# MCU.net
KiCad netlist of a schematic drawn in Altium Designer
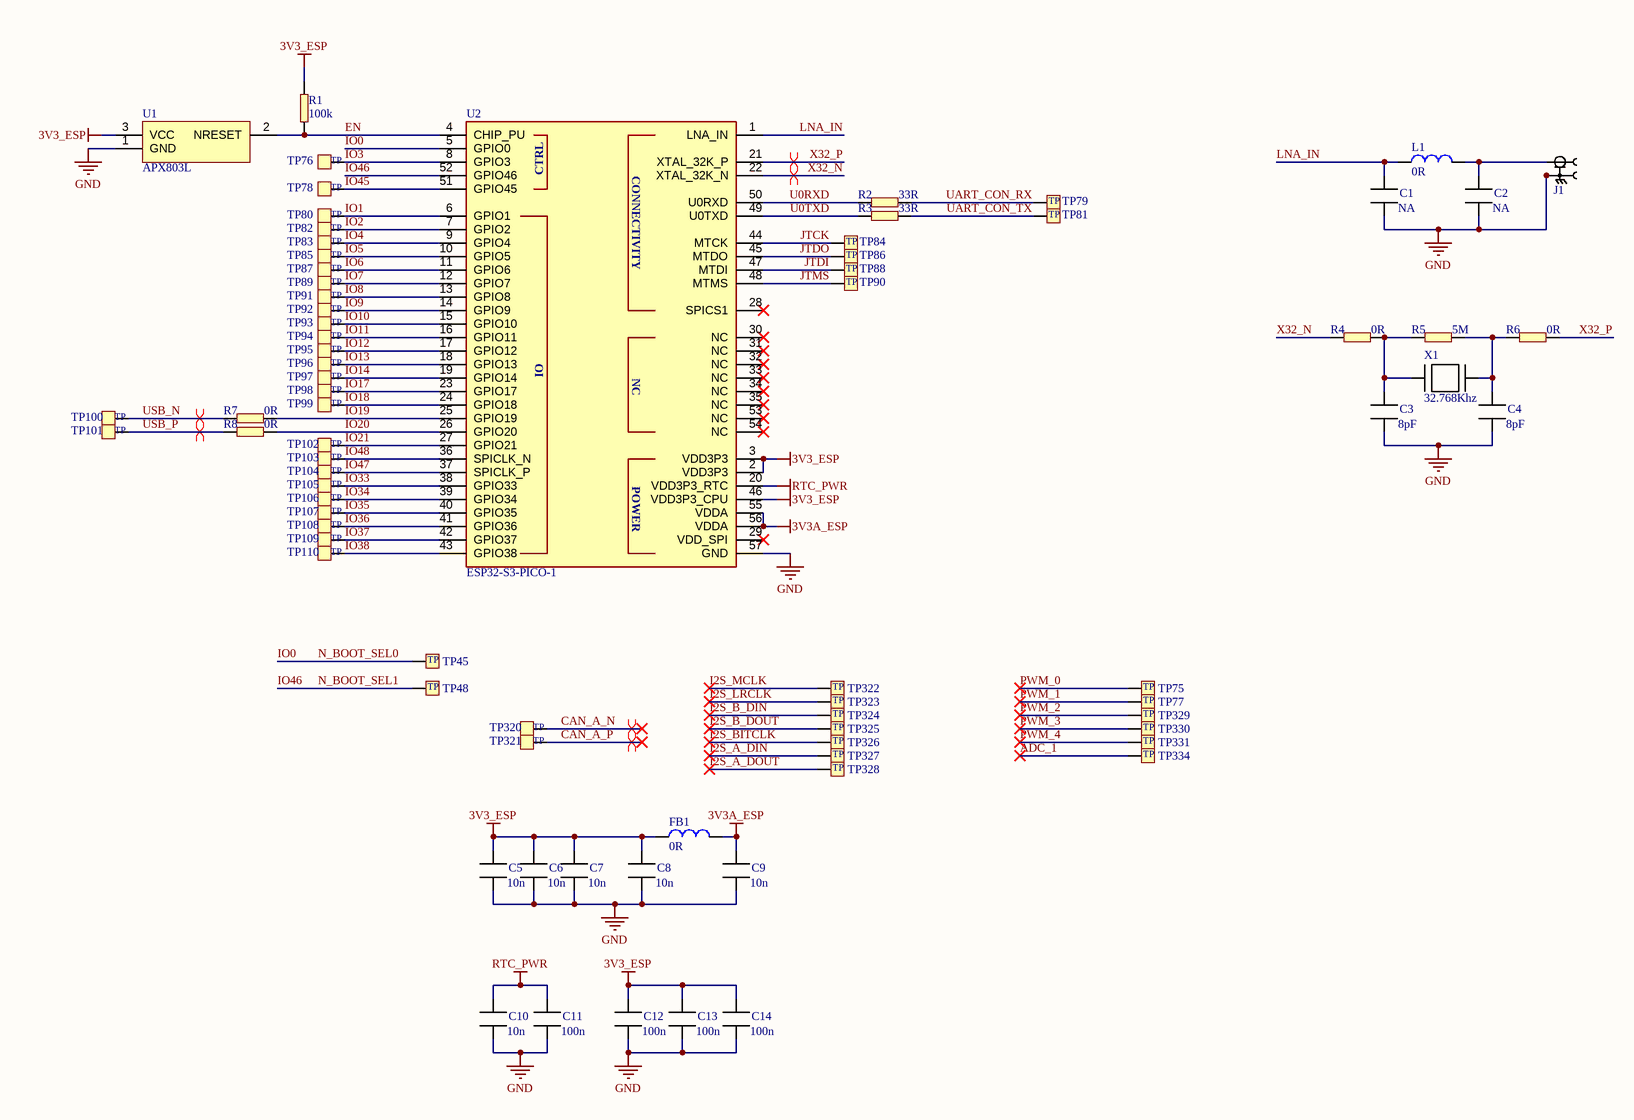
[diagram p0: MCU.SchDoc]

(export (version "E")
  (design (tool "Eeschema 10.0.6"))
  (components
    (comp (ref "C1")
      (value "NA")
      (footprint "CAPC0603X03L")
      (description "Chip Capacitor, 2-Leads, Body 0.60x0.30mm, IPC High Density")
      (fields (field (name "Comment") "ERP_102-1"))
      (libsource (lib "Capacitor") (part "MLCC_0201"))
    )
    (comp (ref "C2")
      (value "NA")
      (footprint "CAPC0603X03L")
      (description "Chip Capacitor, 2-Leads, Body 0.60x0.30mm, IPC High Density")
      (fields (field (name "Comment") "ERP_102-1"))
      (libsource (lib "Capacitor") (part "MLCC_0201"))
    )
    (comp (ref "C3")
      (value "8pF")
      (footprint "CAPC0603X03L")
      (description "Chip Capacitor, 2-Leads, Body 0.60x0.30mm, IPC High Density")
      (fields (field (name "Comment") "ERP_102-1"))
      (libsource (lib "Capacitor") (part "MLCC_0201"))
    )
    (comp (ref "C4")
      (value "8pF")
      (footprint "CAPC0603X03L")
      (description "Chip Capacitor, 2-Leads, Body 0.60x0.30mm, IPC High Density")
      (fields (field (name "Comment") "ERP_102-1"))
      (libsource (lib "Capacitor") (part "MLCC_0201"))
    )
    (comp (ref "C5")
      (value "10n")
      (footprint "CAPC0603X03L")
      (description "Chip Capacitor, 2-Leads, Body 0.60x0.30mm, IPC High Density")
      (fields (field (name "Comment") "ERP_102-1"))
      (libsource (lib "Capacitor") (part "MLCC_0201"))
    )
    (comp (ref "C6")
      (value "10n")
      (footprint "CAPC0603X03L")
      (description "Chip Capacitor, 2-Leads, Body 0.60x0.30mm, IPC High Density")
      (fields (field (name "Comment") "ERP_102-1"))
      (libsource (lib "Capacitor") (part "MLCC_0201"))
    )
    (comp (ref "C7")
      (value "10n")
      (footprint "CAPC0603X03L")
      (description "Chip Capacitor, 2-Leads, Body 0.60x0.30mm, IPC High Density")
      (fields (field (name "Comment") "ERP_102-1"))
      (libsource (lib "Capacitor") (part "MLCC_0201"))
    )
    (comp (ref "C8")
      (value "10n")
      (footprint "CAPC0603X03L")
      (description "Chip Capacitor, 2-Leads, Body 0.60x0.30mm, IPC High Density")
      (fields (field (name "Comment") "ERP_102-1"))
      (libsource (lib "Capacitor") (part "MLCC_0201"))
    )
    (comp (ref "C9")
      (value "10n")
      (footprint "CAPC0603X03L")
      (description "Chip Capacitor, 2-Leads, Body 0.60x0.30mm, IPC High Density")
      (fields (field (name "Comment") "ERP_102-1"))
      (libsource (lib "Capacitor") (part "MLCC_0201"))
    )
    (comp (ref "C10")
      (value "10n")
      (footprint "CAPC0603X03L")
      (description "Chip Capacitor, 2-Leads, Body 0.60x0.30mm, IPC High Density")
      (fields (field (name "Comment") "ERP_102-1"))
      (libsource (lib "Capacitor") (part "MLCC_0201"))
    )
    (comp (ref "C11")
      (value "100n")
      (footprint "CAPC0603X03L")
      (description "Chip Capacitor, 2-Leads, Body 0.60x0.30mm, IPC High Density")
      (fields (field (name "Comment") "ERP_102-1"))
      (libsource (lib "Capacitor") (part "MLCC_0201"))
    )
    (comp (ref "C12")
      (value "100n")
      (footprint "CAPC0603X03L")
      (description "Chip Capacitor, 2-Leads, Body 0.60x0.30mm, IPC High Density")
      (fields (field (name "Comment") "ERP_102-1"))
      (libsource (lib "Capacitor") (part "MLCC_0201"))
    )
    (comp (ref "C13")
      (value "100n")
      (footprint "CAPC0603X03L")
      (description "Chip Capacitor, 2-Leads, Body 0.60x0.30mm, IPC High Density")
      (fields (field (name "Comment") "ERP_102-1"))
      (libsource (lib "Capacitor") (part "MLCC_0201"))
    )
    (comp (ref "C14")
      (value "100n")
      (footprint "CAPC0603X03L")
      (description "Chip Capacitor, 2-Leads, Body 0.60x0.30mm, IPC High Density")
      (fields (field (name "Comment") "ERP_102-1"))
      (libsource (lib "Capacitor") (part "MLCC_0201"))
    )
    (comp (ref "FB1")
      (value "0R")
      (footprint "INDC0603X03L")
      (description "FERRITE BEAD 0201")
      (fields (field (name "Comment") "ERP_103-3"))
      (libsource (lib "FerriteBead") (part "FB_0201"))
    )
    (comp (ref "J1")
      (value "ERP_148-1")
      (footprint "uFL_50R")
      (description "uFL_50R")
      (libsource (lib "RF_Connector") (part "uFL_50R"))
    )
    (comp (ref "L1")
      (value "0R")
      (footprint "IND_0603")
      (description "IND_0603")
      (fields (field (name "Comment") "ERP_103-3"))
      (libsource (lib "Inductor") (part "IND_0603"))
    )
    (comp (ref "R1")
      (value "100k")
      (footprint "RESC0603X03L")
      (description "RES_0201")
      (fields (field (name "Comment") "ERP_101-1"))
      (libsource (lib "Resistor") (part "RES_0201"))
    )
    (comp (ref "R2")
      (value "33R")
      (footprint "RESC0603X03L")
      (description "RES_0201")
      (fields (field (name "Comment") "ERP_101-1"))
      (libsource (lib "") (part "RES_0201_1"))
    )
    (comp (ref "R3")
      (value "33R")
      (footprint "RESC0603X03L")
      (description "RES_0201")
      (fields (field (name "Comment") "ERP_101-1"))
      (libsource (lib "") (part "RES_0201_1"))
    )
    (comp (ref "R4")
      (value "0R")
      (footprint "RESC0603X03L")
      (description "RES_0201")
      (fields (field (name "Comment") "ERP_101-1"))
      (libsource (lib "") (part "RES_0201_1"))
    )
    (comp (ref "R5")
      (value "5M")
      (footprint "RESC0603X03L")
      (description "RES_0201")
      (fields (field (name "Comment") "ERP_101-1"))
      (libsource (lib "") (part "RES_0201_1"))
    )
    (comp (ref "R6")
      (value "0R")
      (footprint "RESC0603X03L")
      (description "RES_0201")
      (fields (field (name "Comment") "ERP_101-1"))
      (libsource (lib "") (part "RES_0201_1"))
    )
    (comp (ref "R7")
      (value "0R")
      (footprint "RESC0603X03L")
      (description "RES_0201")
      (fields (field (name "Comment") "ERP_101-1"))
      (libsource (lib "") (part "RES_0201_1"))
    )
    (comp (ref "R8")
      (value "0R")
      (footprint "RESC0603X03L")
      (description "RES_0201")
      (fields (field (name "Comment") "ERP_101-1"))
      (libsource (lib "") (part "RES_0201_1"))
    )
    (comp (ref "TP45")
      (value "TP_0P8MM")
      (footprint "TP_0P8MM")
      (description "OSM Footprint 0P8 LGA Ball")
      (libsource (lib "") (part "TP_0P8MM_1"))
    )
    (comp (ref "TP48")
      (value "TP_0P8MM")
      (footprint "TP_0P8MM")
      (description "OSM Footprint 0P8 LGA Ball")
      (libsource (lib "") (part "TP_0P8MM_1"))
    )
    (comp (ref "TP75")
      (value "TP_0P8MM")
      (footprint "TP_0P8MM")
      (description "OSM Footprint 0P8 LGA Ball")
      (libsource (lib "") (part "TP_0P8MM_1"))
    )
    (comp (ref "TP76")
      (value "TP_0P8MM")
      (footprint "TP_0P8MM")
      (description "OSM Footprint 0P8 LGA Ball")
      (libsource (lib "Jumper") (part "TP_0P8MM"))
    )
    (comp (ref "TP77")
      (value "TP_0P8MM")
      (footprint "TP_0P8MM")
      (description "OSM Footprint 0P8 LGA Ball")
      (libsource (lib "") (part "TP_0P8MM_1"))
    )
    (comp (ref "TP78")
      (value "TP_0P8MM")
      (footprint "TP_0P8MM")
      (description "OSM Footprint 0P8 LGA Ball")
      (libsource (lib "Jumper") (part "TP_0P8MM"))
    )
    (comp (ref "TP79")
      (value "TP_0P8MM")
      (footprint "TP_0P8MM")
      (description "OSM Footprint 0P8 LGA Ball")
      (libsource (lib "") (part "TP_0P8MM_1"))
    )
    (comp (ref "TP80")
      (value "TP_0P8MM")
      (footprint "TP_0P8MM")
      (description "OSM Footprint 0P8 LGA Ball")
      (libsource (lib "Jumper") (part "TP_0P8MM"))
    )
    (comp (ref "TP81")
      (value "TP_0P8MM")
      (footprint "TP_0P8MM")
      (description "OSM Footprint 0P8 LGA Ball")
      (libsource (lib "") (part "TP_0P8MM_1"))
    )
    (comp (ref "TP82")
      (value "TP_0P8MM")
      (footprint "TP_0P8MM")
      (description "OSM Footprint 0P8 LGA Ball")
      (libsource (lib "Jumper") (part "TP_0P8MM"))
    )
    (comp (ref "TP83")
      (value "TP_0P8MM")
      (footprint "TP_0P8MM")
      (description "OSM Footprint 0P8 LGA Ball")
      (libsource (lib "Jumper") (part "TP_0P8MM"))
    )
    (comp (ref "TP84")
      (value "TP_0P8MM")
      (footprint "TP_0P8MM")
      (description "OSM Footprint 0P8 LGA Ball")
      (libsource (lib "") (part "TP_0P8MM_1"))
    )
    (comp (ref "TP85")
      (value "TP_0P8MM")
      (footprint "TP_0P8MM")
      (description "OSM Footprint 0P8 LGA Ball")
      (libsource (lib "Jumper") (part "TP_0P8MM"))
    )
    (comp (ref "TP86")
      (value "TP_0P8MM")
      (footprint "TP_0P8MM")
      (description "OSM Footprint 0P8 LGA Ball")
      (libsource (lib "") (part "TP_0P8MM_1"))
    )
    (comp (ref "TP87")
      (value "TP_0P8MM")
      (footprint "TP_0P8MM")
      (description "OSM Footprint 0P8 LGA Ball")
      (libsource (lib "Jumper") (part "TP_0P8MM"))
    )
    (comp (ref "TP88")
      (value "TP_0P8MM")
      (footprint "TP_0P8MM")
      (description "OSM Footprint 0P8 LGA Ball")
      (libsource (lib "") (part "TP_0P8MM_1"))
    )
    (comp (ref "TP89")
      (value "TP_0P8MM")
      (footprint "TP_0P8MM")
      (description "OSM Footprint 0P8 LGA Ball")
      (libsource (lib "Jumper") (part "TP_0P8MM"))
    )
    (comp (ref "TP90")
      (value "TP_0P8MM")
      (footprint "TP_0P8MM")
      (description "OSM Footprint 0P8 LGA Ball")
      (libsource (lib "") (part "TP_0P8MM_1"))
    )
    (comp (ref "TP91")
      (value "TP_0P8MM")
      (footprint "TP_0P8MM")
      (description "OSM Footprint 0P8 LGA Ball")
      (libsource (lib "Jumper") (part "TP_0P8MM"))
    )
    (comp (ref "TP92")
      (value "TP_0P8MM")
      (footprint "TP_0P8MM")
      (description "OSM Footprint 0P8 LGA Ball")
      (libsource (lib "Jumper") (part "TP_0P8MM"))
    )
    (comp (ref "TP93")
      (value "TP_0P8MM")
      (footprint "TP_0P8MM")
      (description "OSM Footprint 0P8 LGA Ball")
      (libsource (lib "Jumper") (part "TP_0P8MM"))
    )
    (comp (ref "TP94")
      (value "TP_0P8MM")
      (footprint "TP_0P8MM")
      (description "OSM Footprint 0P8 LGA Ball")
      (libsource (lib "Jumper") (part "TP_0P8MM"))
    )
    (comp (ref "TP95")
      (value "TP_0P8MM")
      (footprint "TP_0P8MM")
      (description "OSM Footprint 0P8 LGA Ball")
      (libsource (lib "Jumper") (part "TP_0P8MM"))
    )
    (comp (ref "TP96")
      (value "TP_0P8MM")
      (footprint "TP_0P8MM")
      (description "OSM Footprint 0P8 LGA Ball")
      (libsource (lib "Jumper") (part "TP_0P8MM"))
    )
    (comp (ref "TP97")
      (value "TP_0P8MM")
      (footprint "TP_0P8MM")
      (description "OSM Footprint 0P8 LGA Ball")
      (libsource (lib "Jumper") (part "TP_0P8MM"))
    )
    (comp (ref "TP98")
      (value "TP_0P8MM")
      (footprint "TP_0P8MM")
      (description "OSM Footprint 0P8 LGA Ball")
      (libsource (lib "Jumper") (part "TP_0P8MM"))
    )
    (comp (ref "TP99")
      (value "TP_0P8MM")
      (footprint "TP_0P8MM")
      (description "OSM Footprint 0P8 LGA Ball")
      (libsource (lib "Jumper") (part "TP_0P8MM"))
    )
    (comp (ref "TP100")
      (value "TP_0P8MM")
      (footprint "TP_0P8MM")
      (description "OSM Footprint 0P8 LGA Ball")
      (libsource (lib "Jumper") (part "TP_0P8MM"))
    )
    (comp (ref "TP101")
      (value "TP_0P8MM")
      (footprint "TP_0P8MM")
      (description "OSM Footprint 0P8 LGA Ball")
      (libsource (lib "Jumper") (part "TP_0P8MM"))
    )
    (comp (ref "TP102")
      (value "TP_0P8MM")
      (footprint "TP_0P8MM")
      (description "OSM Footprint 0P8 LGA Ball")
      (libsource (lib "Jumper") (part "TP_0P8MM"))
    )
    (comp (ref "TP103")
      (value "TP_0P8MM")
      (footprint "TP_0P8MM")
      (description "OSM Footprint 0P8 LGA Ball")
      (libsource (lib "Jumper") (part "TP_0P8MM"))
    )
    (comp (ref "TP104")
      (value "TP_0P8MM")
      (footprint "TP_0P8MM")
      (description "OSM Footprint 0P8 LGA Ball")
      (libsource (lib "Jumper") (part "TP_0P8MM"))
    )
    (comp (ref "TP105")
      (value "TP_0P8MM")
      (footprint "TP_0P8MM")
      (description "OSM Footprint 0P8 LGA Ball")
      (libsource (lib "Jumper") (part "TP_0P8MM"))
    )
    (comp (ref "TP106")
      (value "TP_0P8MM")
      (footprint "TP_0P8MM")
      (description "OSM Footprint 0P8 LGA Ball")
      (libsource (lib "Jumper") (part "TP_0P8MM"))
    )
    (comp (ref "TP107")
      (value "TP_0P8MM")
      (footprint "TP_0P8MM")
      (description "OSM Footprint 0P8 LGA Ball")
      (libsource (lib "Jumper") (part "TP_0P8MM"))
    )
    (comp (ref "TP108")
      (value "TP_0P8MM")
      (footprint "TP_0P8MM")
      (description "OSM Footprint 0P8 LGA Ball")
      (libsource (lib "Jumper") (part "TP_0P8MM"))
    )
    (comp (ref "TP109")
      (value "TP_0P8MM")
      (footprint "TP_0P8MM")
      (description "OSM Footprint 0P8 LGA Ball")
      (libsource (lib "Jumper") (part "TP_0P8MM"))
    )
    (comp (ref "TP110")
      (value "TP_0P8MM")
      (footprint "TP_0P8MM")
      (description "OSM Footprint 0P8 LGA Ball")
      (libsource (lib "Jumper") (part "TP_0P8MM"))
    )
    (comp (ref "TP320")
      (value "TP_0P8MM")
      (footprint "TP_0P8MM")
      (description "OSM Footprint 0P8 LGA Ball")
      (libsource (lib "Jumper") (part "TP_0P8MM"))
    )
    (comp (ref "TP321")
      (value "TP_0P8MM")
      (footprint "TP_0P8MM")
      (description "OSM Footprint 0P8 LGA Ball")
      (libsource (lib "Jumper") (part "TP_0P8MM"))
    )
    (comp (ref "TP322")
      (value "TP_0P8MM")
      (footprint "TP_0P8MM")
      (description "OSM Footprint 0P8 LGA Ball")
      (libsource (lib "") (part "TP_0P8MM_1"))
    )
    (comp (ref "TP323")
      (value "TP_0P8MM")
      (footprint "TP_0P8MM")
      (description "OSM Footprint 0P8 LGA Ball")
      (libsource (lib "") (part "TP_0P8MM_1"))
    )
    (comp (ref "TP324")
      (value "TP_0P8MM")
      (footprint "TP_0P8MM")
      (description "OSM Footprint 0P8 LGA Ball")
      (libsource (lib "") (part "TP_0P8MM_1"))
    )
    (comp (ref "TP325")
      (value "TP_0P8MM")
      (footprint "TP_0P8MM")
      (description "OSM Footprint 0P8 LGA Ball")
      (libsource (lib "") (part "TP_0P8MM_1"))
    )
    (comp (ref "TP326")
      (value "TP_0P8MM")
      (footprint "TP_0P8MM")
      (description "OSM Footprint 0P8 LGA Ball")
      (libsource (lib "") (part "TP_0P8MM_1"))
    )
    (comp (ref "TP327")
      (value "TP_0P8MM")
      (footprint "TP_0P8MM")
      (description "OSM Footprint 0P8 LGA Ball")
      (libsource (lib "") (part "TP_0P8MM_1"))
    )
    (comp (ref "TP328")
      (value "TP_0P8MM")
      (footprint "TP_0P8MM")
      (description "OSM Footprint 0P8 LGA Ball")
      (libsource (lib "") (part "TP_0P8MM_1"))
    )
    (comp (ref "TP329")
      (value "TP_0P8MM")
      (footprint "TP_0P8MM")
      (description "OSM Footprint 0P8 LGA Ball")
      (libsource (lib "") (part "TP_0P8MM_1"))
    )
    (comp (ref "TP330")
      (value "TP_0P8MM")
      (footprint "TP_0P8MM")
      (description "OSM Footprint 0P8 LGA Ball")
      (libsource (lib "") (part "TP_0P8MM_1"))
    )
    (comp (ref "TP331")
      (value "TP_0P8MM")
      (footprint "TP_0P8MM")
      (description "OSM Footprint 0P8 LGA Ball")
      (libsource (lib "") (part "TP_0P8MM_1"))
    )
    (comp (ref "TP334")
      (value "TP_0P8MM")
      (footprint "TP_0P8MM")
      (description "OSM Footprint 0P8 LGA Ball")
      (libsource (lib "") (part "TP_0P8MM_1"))
    )
    (comp (ref "U1")
      (value "APX803L")
      (footprint "APX803L")
      (description "IC SUPERVISOR 1 CHANNEL SOT23")
      (libsource (lib "VoltageDetector") (part "APX803L"))
    )
    (comp (ref "U2")
      (value "ESP32-S3-PICO-1")
      (footprint "QFN40P700X700X106_HS-57N")
      (description "RF TXRX MOD BLUETOOTH WIFISMD")
      (fields (field (name "Comment") "ERP_121-4"))
      (libsource (lib "RF-IC") (part "ESP32-S3-PICO-1"))
    )
    (comp (ref "X1")
      (value "32.768Khz")
      (footprint "CRYS_L1.6_W1")
      (description "CRYSTAL 1P6XW1P0")
      (fields (field (name "Comment") "ERP_111-1"))
      (libsource (lib "Crystal") (part "CRYS_L1.6_W1"))
    )
  )
  (nets
    (net (code "2") (name "/ADC_1") (class "Default")
      (node (ref "TP334") (pin "1") (pinfunction "1_1") (pintype "passive+no_connect"))
    )
    (net (code "3") (name "/CAN_A_N") (class "Default")
      (node (ref "TP320") (pin "1") (pinfunction "1_1") (pintype "passive+no_connect"))
    )
    (net (code "4") (name "/CAN_A_P") (class "Default")
      (node (ref "TP321") (pin "1") (pinfunction "1_1") (pintype "passive+no_connect"))
    )
    (net (code "5") (name "/EN") (class "Default")
      (node (ref "R1") (pin "1") (pinfunction "1_1") (pintype "passive"))
      (node (ref "U1") (pin "2") (pinfunction "NRESET_2") (pintype "passive"))
      (node (ref "U2") (pin "4") (pinfunction "CHIP_PU_4") (pintype "passive"))
    )
    (net (code "6") (name "/I2S_A_DIN") (class "Default")
      (node (ref "TP327") (pin "1") (pinfunction "1_1") (pintype "passive+no_connect"))
    )
    (net (code "7") (name "/I2S_A_DOUT") (class "Default")
      (node (ref "TP328") (pin "1") (pinfunction "1_1") (pintype "passive+no_connect"))
    )
    (net (code "8") (name "/I2S_BITCLK") (class "Default")
      (node (ref "TP326") (pin "1") (pinfunction "1_1") (pintype "passive+no_connect"))
    )
    (net (code "9") (name "/I2S_B_DIN") (class "Default")
      (node (ref "TP324") (pin "1") (pinfunction "1_1") (pintype "passive+no_connect"))
    )
    (net (code "10") (name "/I2S_B_DOUT") (class "Default")
      (node (ref "TP325") (pin "1") (pinfunction "1_1") (pintype "passive+no_connect"))
    )
    (net (code "11") (name "/I2S_LRCLK") (class "Default")
      (node (ref "TP323") (pin "1") (pinfunction "1_1") (pintype "passive+no_connect"))
    )
    (net (code "12") (name "/I2S_MCLK") (class "Default")
      (node (ref "TP322") (pin "1") (pinfunction "1_1") (pintype "passive+no_connect"))
    )
    (net (code "13") (name "/IO0") (class "Default")
      (node (ref "TP45") (pin "1") (pinfunction "1_1") (pintype "passive"))
      (node (ref "U2") (pin "5") (pinfunction "GPIO0_5") (pintype "passive"))
    )
    (net (code "14") (name "/IO1") (class "Default")
      (node (ref "TP80") (pin "1") (pinfunction "1_1") (pintype "passive"))
      (node (ref "U2") (pin "6") (pinfunction "GPIO1_6") (pintype "passive"))
    )
    (net (code "15") (name "/IO2") (class "Default")
      (node (ref "TP82") (pin "1") (pinfunction "1_1") (pintype "passive"))
      (node (ref "U2") (pin "7") (pinfunction "GPIO2_7") (pintype "passive"))
    )
    (net (code "16") (name "/IO3") (class "Default")
      (node (ref "TP76") (pin "1") (pinfunction "1_1") (pintype "passive"))
      (node (ref "U2") (pin "8") (pinfunction "GPIO3_8") (pintype "passive"))
    )
    (net (code "17") (name "/IO4") (class "Default")
      (node (ref "TP83") (pin "1") (pinfunction "1_1") (pintype "passive"))
      (node (ref "U2") (pin "9") (pinfunction "GPIO4_9") (pintype "passive"))
    )
    (net (code "18") (name "/IO5") (class "Default")
      (node (ref "TP85") (pin "1") (pinfunction "1_1") (pintype "passive"))
      (node (ref "U2") (pin "10") (pinfunction "GPIO5_10") (pintype "passive"))
    )
    (net (code "19") (name "/IO6") (class "Default")
      (node (ref "TP87") (pin "1") (pinfunction "1_1") (pintype "passive"))
      (node (ref "U2") (pin "11") (pinfunction "GPIO6_11") (pintype "passive"))
    )
    (net (code "20") (name "/IO7") (class "Default")
      (node (ref "TP89") (pin "1") (pinfunction "1_1") (pintype "passive"))
      (node (ref "U2") (pin "12") (pinfunction "GPIO7_12") (pintype "passive"))
    )
    (net (code "21") (name "/IO8") (class "Default")
      (node (ref "TP91") (pin "1") (pinfunction "1_1") (pintype "passive"))
      (node (ref "U2") (pin "13") (pinfunction "GPIO8_13") (pintype "passive"))
    )
    (net (code "22") (name "/IO9") (class "Default")
      (node (ref "TP92") (pin "1") (pinfunction "1_1") (pintype "passive"))
      (node (ref "U2") (pin "14") (pinfunction "GPIO9_14") (pintype "passive"))
    )
    (net (code "23") (name "/IO10") (class "Default")
      (node (ref "TP93") (pin "1") (pinfunction "1_1") (pintype "passive"))
      (node (ref "U2") (pin "15") (pinfunction "GPIO10_15") (pintype "passive"))
    )
    (net (code "24") (name "/IO11") (class "Default")
      (node (ref "TP94") (pin "1") (pinfunction "1_1") (pintype "passive"))
      (node (ref "U2") (pin "16") (pinfunction "GPIO11_16") (pintype "passive"))
    )
    (net (code "25") (name "/IO12") (class "Default")
      (node (ref "TP95") (pin "1") (pinfunction "1_1") (pintype "passive"))
      (node (ref "U2") (pin "17") (pinfunction "GPIO12_17") (pintype "passive"))
    )
    (net (code "26") (name "/IO13") (class "Default")
      (node (ref "TP96") (pin "1") (pinfunction "1_1") (pintype "passive"))
      (node (ref "U2") (pin "18") (pinfunction "GPIO13_18") (pintype "passive"))
    )
    (net (code "27") (name "/IO14") (class "Default")
      (node (ref "TP97") (pin "1") (pinfunction "1_1") (pintype "passive"))
      (node (ref "U2") (pin "19") (pinfunction "GPIO14_19") (pintype "passive"))
    )
    (net (code "28") (name "/IO17") (class "Default")
      (node (ref "TP98") (pin "1") (pinfunction "1_1") (pintype "passive"))
      (node (ref "U2") (pin "23") (pinfunction "GPIO17_23") (pintype "passive"))
    )
    (net (code "29") (name "/IO18") (class "Default")
      (node (ref "TP99") (pin "1") (pinfunction "1_1") (pintype "passive"))
      (node (ref "U2") (pin "24") (pinfunction "GPIO18_24") (pintype "passive"))
    )
    (net (code "30") (name "/IO19") (class "Default")
      (node (ref "R7") (pin "1") (pinfunction "1_1") (pintype "passive"))
      (node (ref "U2") (pin "25") (pinfunction "GPIO19_25") (pintype "passive"))
    )
    (net (code "31") (name "/IO20") (class "Default")
      (node (ref "R8") (pin "1") (pinfunction "1_1") (pintype "passive"))
      (node (ref "U2") (pin "26") (pinfunction "GPIO20_26") (pintype "passive"))
    )
    (net (code "32") (name "/IO21") (class "Default")
      (node (ref "TP102") (pin "1") (pinfunction "1_1") (pintype "passive"))
      (node (ref "U2") (pin "27") (pinfunction "GPIO21_27") (pintype "passive"))
    )
    (net (code "33") (name "/IO33") (class "Default")
      (node (ref "TP105") (pin "1") (pinfunction "1_1") (pintype "passive"))
      (node (ref "U2") (pin "38") (pinfunction "GPIO33_38") (pintype "passive"))
    )
    (net (code "34") (name "/IO34") (class "Default")
      (node (ref "TP106") (pin "1") (pinfunction "1_1") (pintype "passive"))
      (node (ref "U2") (pin "39") (pinfunction "GPIO34_39") (pintype "passive"))
    )
    (net (code "35") (name "/IO35") (class "Default")
      (node (ref "TP107") (pin "1") (pinfunction "1_1") (pintype "passive"))
      (node (ref "U2") (pin "40") (pinfunction "GPIO35_40") (pintype "passive"))
    )
    (net (code "36") (name "/IO36") (class "Default")
      (node (ref "TP108") (pin "1") (pinfunction "1_1") (pintype "passive"))
      (node (ref "U2") (pin "41") (pinfunction "GPIO36_41") (pintype "passive"))
    )
    (net (code "37") (name "/IO37") (class "Default")
      (node (ref "TP109") (pin "1") (pinfunction "1_1") (pintype "passive"))
      (node (ref "U2") (pin "42") (pinfunction "GPIO37_42") (pintype "passive"))
    )
    (net (code "38") (name "/IO38") (class "Default")
      (node (ref "TP110") (pin "1") (pinfunction "1_1") (pintype "passive"))
      (node (ref "U2") (pin "43") (pinfunction "GPIO38_43") (pintype "passive"))
    )
    (net (code "39") (name "/IO45") (class "Default")
      (node (ref "TP78") (pin "1") (pinfunction "1_1") (pintype "passive"))
      (node (ref "U2") (pin "51") (pinfunction "GPIO45_51") (pintype "passive"))
    )
    (net (code "40") (name "/IO46") (class "Default")
      (node (ref "TP48") (pin "1") (pinfunction "1_1") (pintype "passive"))
      (node (ref "U2") (pin "52") (pinfunction "GPIO46_52") (pintype "passive"))
    )
    (net (code "41") (name "/IO47") (class "Default")
      (node (ref "TP104") (pin "1") (pinfunction "1_1") (pintype "passive"))
      (node (ref "U2") (pin "37") (pinfunction "SPICLK_P_37") (pintype "passive"))
    )
    (net (code "42") (name "/IO48") (class "Default")
      (node (ref "TP103") (pin "1") (pinfunction "1_1") (pintype "passive"))
      (node (ref "U2") (pin "36") (pinfunction "SPICLK_N_36") (pintype "passive"))
    )
    (net (code "43") (name "/JTCK") (class "Default")
      (node (ref "TP84") (pin "1") (pinfunction "1_1") (pintype "passive"))
      (node (ref "U2") (pin "44") (pinfunction "MTCK_44") (pintype "passive"))
    )
    (net (code "44") (name "/JTDI") (class "Default")
      (node (ref "TP88") (pin "1") (pinfunction "1_1") (pintype "passive"))
      (node (ref "U2") (pin "47") (pinfunction "MTDI_47") (pintype "passive"))
    )
    (net (code "45") (name "/JTDO") (class "Default")
      (node (ref "TP86") (pin "1") (pinfunction "1_1") (pintype "passive"))
      (node (ref "U2") (pin "45") (pinfunction "MTDO_45") (pintype "passive"))
    )
    (net (code "46") (name "/JTMS") (class "Default")
      (node (ref "TP90") (pin "1") (pinfunction "1_1") (pintype "passive"))
      (node (ref "U2") (pin "48") (pinfunction "MTMS_48") (pintype "passive"))
    )
    (net (code "47") (name "/LNA_IN") (class "Default")
      (node (ref "C1") (pin "1") (pinfunction "1_1") (pintype "passive"))
      (node (ref "L1") (pin "1") (pinfunction "1_1") (pintype "passive"))
      (node (ref "U2") (pin "1") (pinfunction "LNA_IN_1") (pintype "passive"))
    )
    (net (code "48") (name "/PWM_0") (class "Default")
      (node (ref "TP75") (pin "1") (pinfunction "1_1") (pintype "passive+no_connect"))
    )
    (net (code "49") (name "/PWM_1") (class "Default")
      (node (ref "TP77") (pin "1") (pinfunction "1_1") (pintype "passive+no_connect"))
    )
    (net (code "50") (name "/PWM_2") (class "Default")
      (node (ref "TP329") (pin "1") (pinfunction "1_1") (pintype "passive+no_connect"))
    )
    (net (code "51") (name "/PWM_3") (class "Default")
      (node (ref "TP330") (pin "1") (pinfunction "1_1") (pintype "passive+no_connect"))
    )
    (net (code "52") (name "/PWM_4") (class "Default")
      (node (ref "TP331") (pin "1") (pinfunction "1_1") (pintype "passive+no_connect"))
    )
    (net (code "53") (name "/U0RXD") (class "Default")
      (node (ref "R2") (pin "2") (pinfunction "2_2") (pintype "passive"))
      (node (ref "U2") (pin "50") (pinfunction "U0RXD_50") (pintype "passive"))
    )
    (net (code "54") (name "/U0TXD") (class "Default")
      (node (ref "R3") (pin "2") (pinfunction "2_2") (pintype "passive"))
      (node (ref "U2") (pin "49") (pinfunction "U0TXD_49") (pintype "passive"))
    )
    (net (code "55") (name "/UART_CON_RX") (class "Default")
      (node (ref "R2") (pin "1") (pinfunction "1_1") (pintype "passive"))
      (node (ref "TP79") (pin "1") (pinfunction "1_1") (pintype "passive"))
    )
    (net (code "56") (name "/UART_CON_TX") (class "Default")
      (node (ref "R3") (pin "1") (pinfunction "1_1") (pintype "passive"))
      (node (ref "TP81") (pin "1") (pinfunction "1_1") (pintype "passive"))
    )
    (net (code "57") (name "/USB_N") (class "Default")
      (node (ref "R7") (pin "2") (pinfunction "2_2") (pintype "passive"))
      (node (ref "TP100") (pin "1") (pinfunction "1_1") (pintype "passive"))
    )
    (net (code "58") (name "/USB_P") (class "Default")
      (node (ref "R8") (pin "2") (pinfunction "2_2") (pintype "passive"))
      (node (ref "TP101") (pin "1") (pinfunction "1_1") (pintype "passive"))
    )
    (net (code "59") (name "/X32_N") (class "Default")
      (node (ref "R4") (pin "2") (pinfunction "2_2") (pintype "passive"))
      (node (ref "U2") (pin "22") (pinfunction "XTAL_32K_N_22") (pintype "passive"))
    )
    (net (code "60") (name "/X32_P") (class "Default")
      (node (ref "R6") (pin "1") (pinfunction "1_1") (pintype "passive"))
      (node (ref "U2") (pin "21") (pinfunction "XTAL_32K_P_21") (pintype "passive"))
    )
    (net (code "61") (name "3V3A_ESP") (class "Default")
      (node (ref "C9") (pin "1") (pinfunction "1_1") (pintype "passive"))
      (node (ref "FB1") (pin "2") (pinfunction "2_2") (pintype "passive"))
      (node (ref "U2") (pin "55") (pinfunction "VDDA_55") (pintype "passive"))
      (node (ref "U2") (pin "56") (pinfunction "VDDA_56") (pintype "passive"))
    )
    (net (code "62") (name "3V3_ESP") (class "Default")
      (node (ref "C12") (pin "1") (pinfunction "1_1") (pintype "passive"))
      (node (ref "C13") (pin "1") (pinfunction "1_1") (pintype "passive"))
      (node (ref "C14") (pin "1") (pinfunction "1_1") (pintype "passive"))
      (node (ref "C5") (pin "1") (pinfunction "1_1") (pintype "passive"))
      (node (ref "C6") (pin "1") (pinfunction "1_1") (pintype "passive"))
      (node (ref "C7") (pin "1") (pinfunction "1_1") (pintype "passive"))
      (node (ref "C8") (pin "1") (pinfunction "1_1") (pintype "passive"))
      (node (ref "FB1") (pin "1") (pinfunction "1_1") (pintype "passive"))
      (node (ref "R1") (pin "2") (pinfunction "2_2") (pintype "passive"))
      (node (ref "U1") (pin "3") (pinfunction "VCC_3") (pintype "passive"))
      (node (ref "U2") (pin "2") (pinfunction "VDD3P3_2") (pintype "passive"))
      (node (ref "U2") (pin "3") (pinfunction "VDD3P3_3") (pintype "passive"))
      (node (ref "U2") (pin "46") (pinfunction "VDD3P3_CPU_46") (pintype "passive"))
    )
    (net (code "63") (name "GND") (class "Default")
      (node (ref "C1") (pin "2") (pinfunction "2_2") (pintype "passive"))
      (node (ref "C10") (pin "2") (pinfunction "2_2") (pintype "passive"))
      (node (ref "C11") (pin "2") (pinfunction "2_2") (pintype "passive"))
      (node (ref "C12") (pin "2") (pinfunction "2_2") (pintype "passive"))
      (node (ref "C13") (pin "2") (pinfunction "2_2") (pintype "passive"))
      (node (ref "C14") (pin "2") (pinfunction "2_2") (pintype "passive"))
      (node (ref "C2") (pin "2") (pinfunction "2_2") (pintype "passive"))
      (node (ref "C3") (pin "2") (pinfunction "2_2") (pintype "passive"))
      (node (ref "C4") (pin "2") (pinfunction "2_2") (pintype "passive"))
      (node (ref "C5") (pin "2") (pinfunction "2_2") (pintype "passive"))
      (node (ref "C6") (pin "2") (pinfunction "2_2") (pintype "passive"))
      (node (ref "C7") (pin "2") (pinfunction "2_2") (pintype "passive"))
      (node (ref "C8") (pin "2") (pinfunction "2_2") (pintype "passive"))
      (node (ref "C9") (pin "2") (pinfunction "2_2") (pintype "passive"))
      (node (ref "J1") (pin "2") (pinfunction "2_2") (pintype "passive"))
      (node (ref "J1") (pin "3") (pinfunction "2_3") (pintype "passive"))
      (node (ref "U1") (pin "1") (pinfunction "GND_1") (pintype "passive"))
      (node (ref "U2") (pin "57") (pinfunction "GND_57") (pintype "passive"))
    )
    (net (code "64") (name "Net-(C2-Pad1)") (class "Default")
      (node (ref "C2") (pin "1") (pinfunction "1_1") (pintype "passive"))
      (node (ref "J1") (pin "1") (pinfunction "1_1") (pintype "passive"))
      (node (ref "L1") (pin "2") (pinfunction "2_2") (pintype "passive"))
    )
    (net (code "65") (name "Net-(C3-Pad1)") (class "Default")
      (node (ref "C3") (pin "1") (pinfunction "1_1") (pintype "passive"))
      (node (ref "R4") (pin "1") (pinfunction "1_1") (pintype "passive"))
      (node (ref "R5") (pin "2") (pinfunction "2_2") (pintype "passive"))
      (node (ref "X1") (pin "1") (pinfunction "1_1") (pintype "passive"))
    )
    (net (code "66") (name "Net-(C4-Pad1)") (class "Default")
      (node (ref "C4") (pin "1") (pinfunction "1_1") (pintype "passive"))
      (node (ref "R5") (pin "1") (pinfunction "1_1") (pintype "passive"))
      (node (ref "R6") (pin "2") (pinfunction "2_2") (pintype "passive"))
      (node (ref "X1") (pin "2") (pinfunction "2_2") (pintype "passive"))
    )
    (net (code "67") (name "RTC_PWR") (class "Default")
      (node (ref "C10") (pin "1") (pinfunction "1_1") (pintype "passive"))
      (node (ref "C11") (pin "1") (pinfunction "1_1") (pintype "passive"))
      (node (ref "U2") (pin "20") (pinfunction "VDD3P3_RTC_20") (pintype "passive"))
    )
    (net (code "68") (name "unconnected-(U2-NC-Pad30)") (class "Default")
      (node (ref "U2") (pin "30") (pinfunction "NC_30") (pintype "passive+no_connect"))
    )
    (net (code "69") (name "unconnected-(U2-NC-Pad31)") (class "Default")
      (node (ref "U2") (pin "31") (pinfunction "NC_31") (pintype "passive+no_connect"))
    )
    (net (code "70") (name "unconnected-(U2-NC-Pad32)") (class "Default")
      (node (ref "U2") (pin "32") (pinfunction "NC_32") (pintype "passive+no_connect"))
    )
    (net (code "71") (name "unconnected-(U2-NC-Pad33)") (class "Default")
      (node (ref "U2") (pin "33") (pinfunction "NC_33") (pintype "passive+no_connect"))
    )
    (net (code "72") (name "unconnected-(U2-NC-Pad34)") (class "Default")
      (node (ref "U2") (pin "34") (pinfunction "NC_34") (pintype "passive+no_connect"))
    )
    (net (code "73") (name "unconnected-(U2-NC-Pad35)") (class "Default")
      (node (ref "U2") (pin "35") (pinfunction "NC_35") (pintype "passive+no_connect"))
    )
    (net (code "74") (name "unconnected-(U2-NC-Pad53)") (class "Default")
      (node (ref "U2") (pin "53") (pinfunction "NC_53") (pintype "passive+no_connect"))
    )
    (net (code "75") (name "unconnected-(U2-NC-Pad54)") (class "Default")
      (node (ref "U2") (pin "54") (pinfunction "NC_54") (pintype "passive+no_connect"))
    )
    (net (code "76") (name "unconnected-(U2-SPICS1-Pad28)") (class "Default")
      (node (ref "U2") (pin "28") (pinfunction "SPICS1_28") (pintype "passive+no_connect"))
    )
    (net (code "77") (name "unconnected-(U2-VDD_SPI-Pad29)") (class "Default")
      (node (ref "U2") (pin "29") (pinfunction "VDD_SPI_29") (pintype "passive+no_connect"))
    )
  )
)
